# lpc1347_refboard.net
KiCad netlist of a schematic drawn in EAGLE
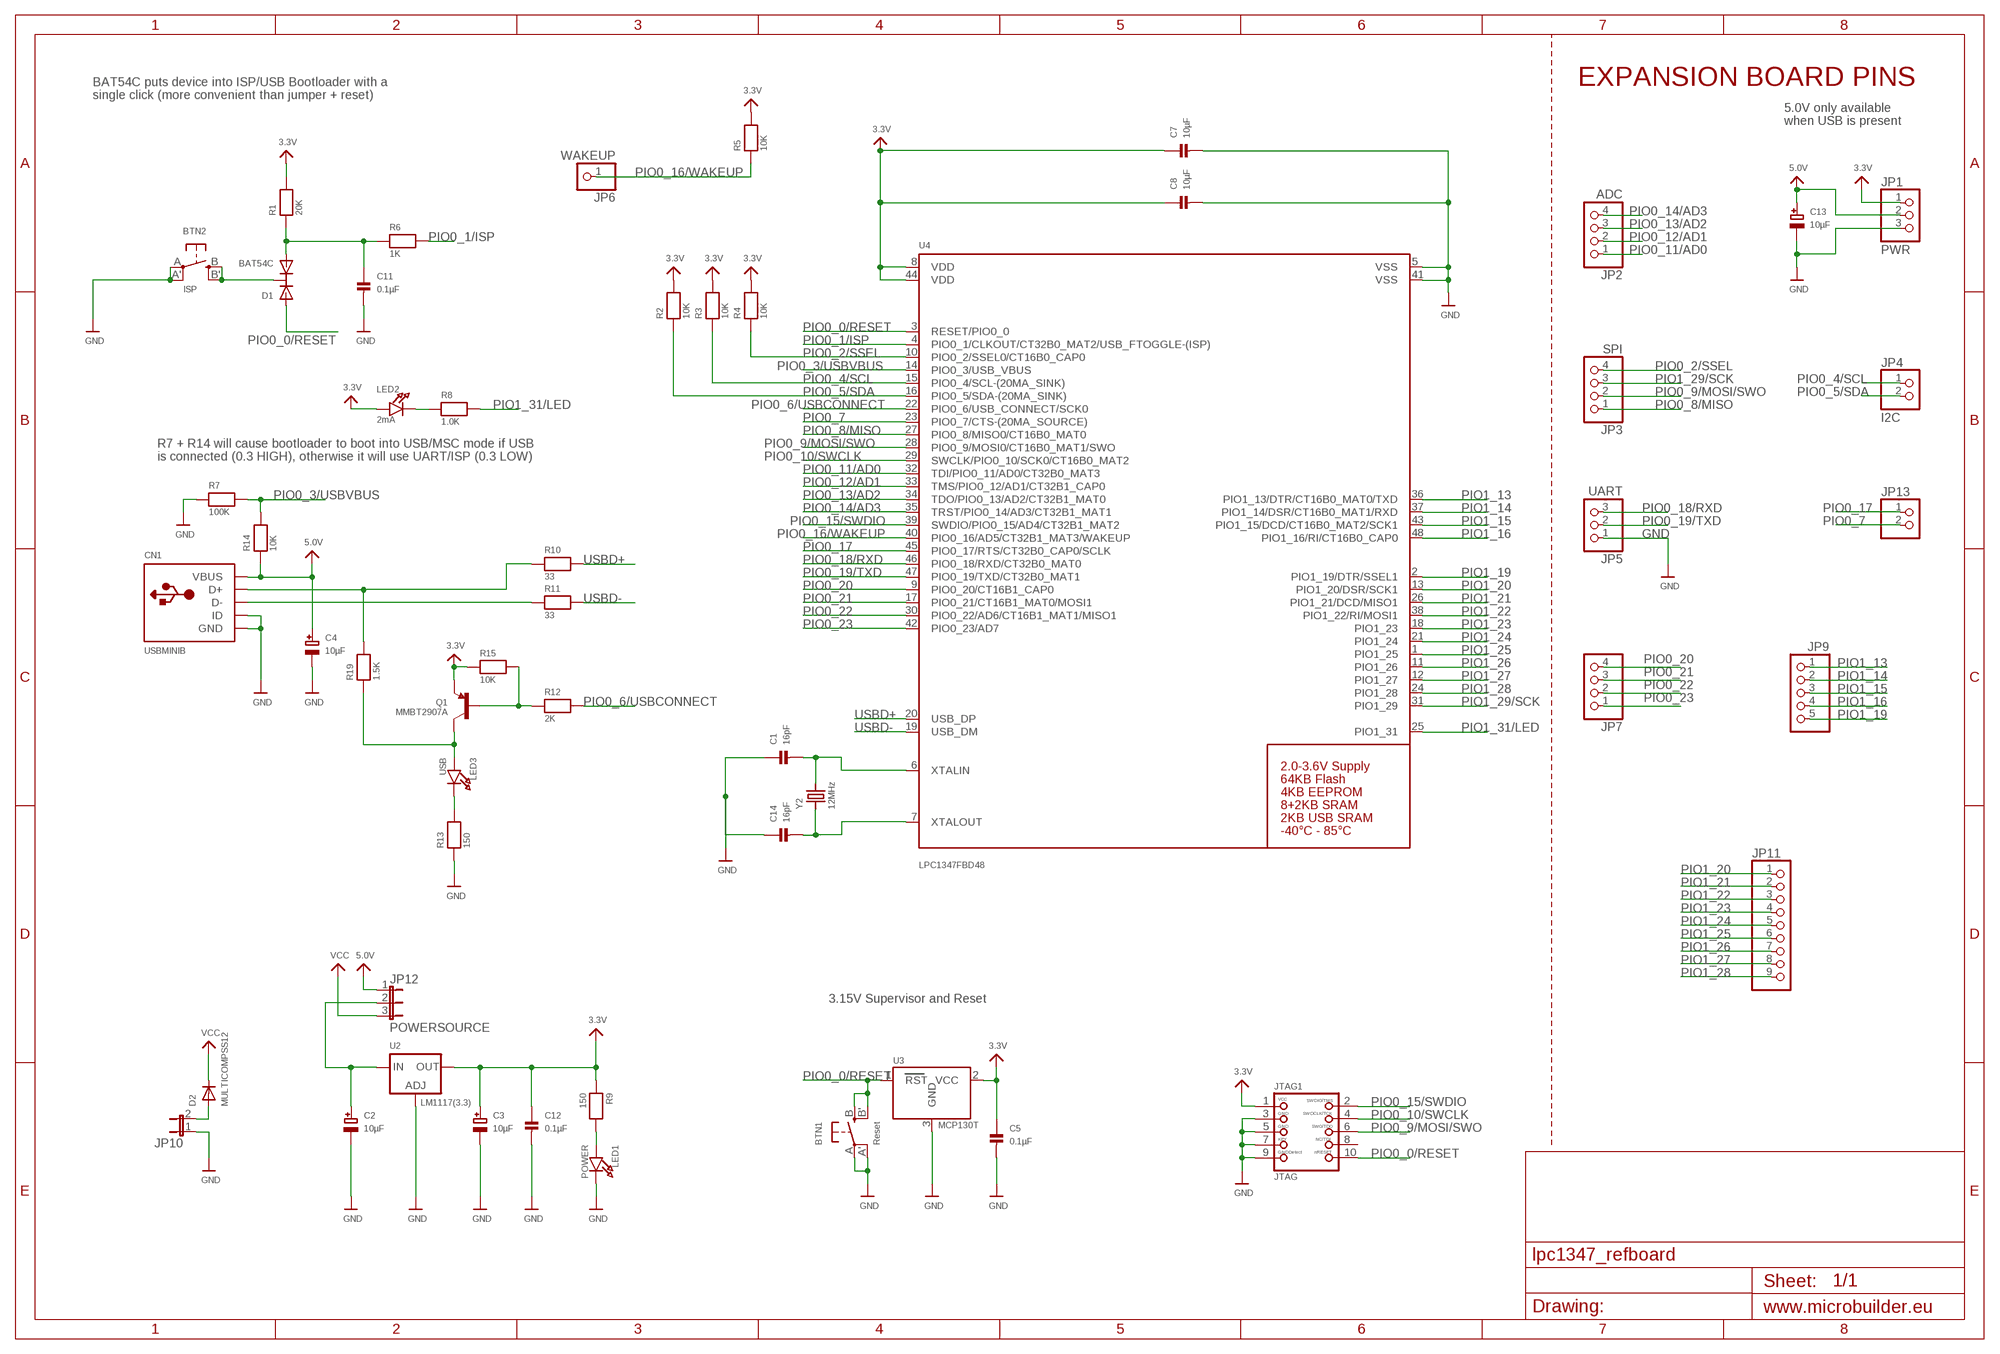
[diagram p0: schematic, sheet 1]

(export (version "E")
  (design (tool "Eeschema 10.0.6"))
  (components
    (comp (ref "BTN1")
      (value "Reset")
      (footprint "eagle-import:EVQ-Q2")
      (libsource (lib "eagle-import") (part "SWITCH_TACT_SMT"))
    )
    (comp (ref "BTN2")
      (value "ISP")
      (footprint "eagle-import:EVQ-Q2")
      (libsource (lib "eagle-import") (part "SWITCH_TACT_SMT"))
    )
    (comp (ref "C1")
      (value "16pF")
      (footprint "eagle-import:0603")
      (libsource (lib "eagle-import") (part "CAP_CERAMIC0603"))
    )
    (comp (ref "C2")
      (value "10µF")
      (footprint "eagle-import:EIA3216-18_A-R")
      (libsource (lib "eagle-import") (part "CAP_TANTALUMA/3216_REFLOW"))
    )
    (comp (ref "C3")
      (value "10µF")
      (footprint "eagle-import:EIA3216-18_A-R")
      (libsource (lib "eagle-import") (part "CAP_TANTALUMA/3216_REFLOW"))
    )
    (comp (ref "C4")
      (value "10µF")
      (footprint "eagle-import:EIA3216-18_A-R")
      (libsource (lib "eagle-import") (part "CAP_TANTALUMA/3216_REFLOW"))
    )
    (comp (ref "C5")
      (value "0.1µF")
      (footprint "eagle-import:0603")
      (libsource (lib "eagle-import") (part "CAP_CERAMIC0603"))
    )
    (comp (ref "C7")
      (value "10µF")
      (footprint "eagle-import:0805")
      (libsource (lib "eagle-import") (part "CAP_CERAMIC0805"))
    )
    (comp (ref "C8")
      (value "10µF")
      (footprint "eagle-import:0805")
      (libsource (lib "eagle-import") (part "CAP_CERAMIC0805"))
    )
    (comp (ref "C11")
      (value "0.1µF")
      (footprint "eagle-import:0603")
      (libsource (lib "eagle-import") (part "CAP_CERAMIC0603"))
    )
    (comp (ref "C12")
      (value "0.1µF")
      (footprint "eagle-import:0603")
      (libsource (lib "eagle-import") (part "CAP_CERAMIC0603"))
    )
    (comp (ref "C13")
      (value "10µF")
      (footprint "eagle-import:EIA3216-18_A-R")
      (libsource (lib "eagle-import") (part "CAP_TANTALUMA/3216_REFLOW"))
    )
    (comp (ref "C14")
      (value "16pF")
      (footprint "eagle-import:0603")
      (libsource (lib "eagle-import") (part "CAP_CERAMIC0603"))
    )
    (comp (ref "CN1")
      (value "USBMINIB")
      (footprint "eagle-import:USB-MINIB")
      (libsource (lib "eagle-import") (part "USBMINIB"))
    )
    (comp (ref "D1")
      (value "BAT54C")
      (footprint "eagle-import:SOT23-R")
      (libsource (lib "eagle-import") (part "BAT54C"))
    )
    (comp (ref "D2")
      (value "MULTICOMPSS12")
      (footprint "eagle-import:SMADIODE")
      (libsource (lib "eagle-import") (part "DIODESMA"))
    )
    (comp (ref "JP1")
      (value "PWR")
      (footprint "eagle-import:1X03_ROUND")
      (libsource (lib "eagle-import") (part "HEADER-1X3ROUND"))
    )
    (comp (ref "JP2")
      (value "ADC")
      (footprint "eagle-import:1X04_ROUND")
      (libsource (lib "eagle-import") (part "HEADER-1X4ROUND"))
    )
    (comp (ref "JP3")
      (value "SPI")
      (footprint "eagle-import:1X04_ROUND")
      (libsource (lib "eagle-import") (part "HEADER-1X4ROUND"))
    )
    (comp (ref "JP4")
      (value "I2C")
      (footprint "eagle-import:1X02_ROUND")
      (libsource (lib "eagle-import") (part "HEADER-1X2ROUND"))
    )
    (comp (ref "JP5")
      (value "UART")
      (footprint "eagle-import:1X03_ROUND")
      (libsource (lib "eagle-import") (part "microbuilder (1)_HEADER-1X3ROUND"))
    )
    (comp (ref "JP6")
      (value "WAKEUP")
      (footprint "eagle-import:1X01_ROUND")
      (libsource (lib "eagle-import") (part "HEADER-1X1ROUND"))
    )
    (comp (ref "JP7")
      (value "HEADER-1X4ROUND")
      (footprint "eagle-import:1X04_ROUND")
      (libsource (lib "eagle-import") (part "HEADER-1X4ROUND"))
    )
    (comp (ref "JP9")
      (value "HEADER-1X5ROUND")
      (footprint "eagle-import:1X05_ROUND")
      (libsource (lib "eagle-import") (part "HEADER-1X5ROUND"))
    )
    (comp (ref "JP10")
      (value "JUMPER2")
      (footprint "eagle-import:JUMPER2")
      (libsource (lib "eagle-import") (part "JUMPER2"))
    )
    (comp (ref "JP11")
      (value "HEADER-1X970MIL")
      (footprint "eagle-import:1X09_ROUND_70")
      (libsource (lib "eagle-import") (part "HEADER-1X970MIL"))
    )
    (comp (ref "JP12")
      (value "POWERSOURCE")
      (footprint "eagle-import:JUMPER3")
      (libsource (lib "eagle-import") (part "JUMPER3"))
    )
    (comp (ref "JP13")
      (value "HEADER-1X2ROUND")
      (footprint "eagle-import:1X02_ROUND")
      (libsource (lib "eagle-import") (part "HEADER-1X2ROUND"))
    )
    (comp (ref "JTAG1")
      (value "JTAG")
      (footprint "eagle-import:2X05_1.27MM_SMT")
      (libsource (lib "eagle-import") (part "JTAG-CORTEXM3"))
    )
    (comp (ref "LED1")
      (value "POWER")
      (footprint "eagle-import:CHIPLED_0805")
      (libsource (lib "eagle-import") (part "LED0805"))
    )
    (comp (ref "LED2")
      (value "2mA")
      (footprint "eagle-import:CHIPLED_0805")
      (libsource (lib "eagle-import") (part "LED0805"))
    )
    (comp (ref "LED3")
      (value "USB")
      (footprint "eagle-import:CHIPLED_0805")
      (libsource (lib "eagle-import") (part "LED0805"))
    )
    (comp (ref "Q1")
      (value "MMBT2907A")
      (footprint "eagle-import:SOT23-R")
      (libsource (lib "eagle-import") (part "TRANSISTOR_PNPSOT23-REFLOW"))
    )
    (comp (ref "R1")
      (value "20K")
      (footprint "eagle-import:0603")
      (libsource (lib "eagle-import") (part "RESISTOR0603"))
    )
    (comp (ref "R2")
      (value "10K")
      (footprint "eagle-import:0603")
      (libsource (lib "eagle-import") (part "RESISTOR0603"))
    )
    (comp (ref "R3")
      (value "10K")
      (footprint "eagle-import:0603")
      (libsource (lib "eagle-import") (part "RESISTOR0603"))
    )
    (comp (ref "R4")
      (value "10K")
      (footprint "eagle-import:0603")
      (libsource (lib "eagle-import") (part "RESISTOR0603"))
    )
    (comp (ref "R5")
      (value "10K")
      (footprint "eagle-import:0603")
      (libsource (lib "eagle-import") (part "RESISTOR0603"))
    )
    (comp (ref "R6")
      (value "1K")
      (footprint "eagle-import:0603")
      (libsource (lib "eagle-import") (part "RESISTOR0603"))
    )
    (comp (ref "R7")
      (value "100K")
      (footprint "eagle-import:0603")
      (libsource (lib "eagle-import") (part "RESISTOR0603"))
    )
    (comp (ref "R8")
      (value "1.0K")
      (footprint "eagle-import:0603")
      (libsource (lib "eagle-import") (part "RESISTOR0603"))
    )
    (comp (ref "R9")
      (value "150")
      (footprint "eagle-import:0603")
      (libsource (lib "eagle-import") (part "RESISTOR0603"))
    )
    (comp (ref "R10")
      (value "33")
      (footprint "eagle-import:0603")
      (libsource (lib "eagle-import") (part "RESISTOR0603"))
    )
    (comp (ref "R11")
      (value "33")
      (footprint "eagle-import:0603")
      (libsource (lib "eagle-import") (part "RESISTOR0603"))
    )
    (comp (ref "R12")
      (value "2K")
      (footprint "eagle-import:0603")
      (libsource (lib "eagle-import") (part "RESISTOR0603"))
    )
    (comp (ref "R13")
      (value "150")
      (footprint "eagle-import:0603")
      (libsource (lib "eagle-import") (part "RESISTOR0603"))
    )
    (comp (ref "R14")
      (value "10K")
      (footprint "eagle-import:0603")
      (libsource (lib "eagle-import") (part "RESISTOR0603"))
    )
    (comp (ref "R15")
      (value "10K")
      (footprint "eagle-import:0603")
      (libsource (lib "eagle-import") (part "RESISTOR0603"))
    )
    (comp (ref "R19")
      (value "1.5K")
      (footprint "eagle-import:0603")
      (libsource (lib "eagle-import") (part "RESISTOR0603"))
    )
    (comp (ref "U2")
      (value "LM1117(3.3)")
      (footprint "eagle-import:SOT223-R")
      (libsource (lib "eagle-import") (part "LM1117SOT223-REFLOW"))
    )
    (comp (ref "U3")
      (value "MCP130T")
      (footprint "eagle-import:SOT23-R")
      (libsource (lib "eagle-import") (part "MCP130TREFLOW"))
    )
    (comp (ref "U4")
      (value "LPC1347FBD48")
      (footprint "eagle-import:LQFP48")
      (libsource (lib "eagle-import") (part "LPC1347_QFP48"))
    )
    (comp (ref "Y2")
      (value "12MHz")
      (footprint "eagle-import:CRYSTAL_3.2X2.5")
      (libsource (lib "eagle-import") (part "CRYSTALTHIN"))
    )
  )
  (nets
    (net (code "1") (name "/PIO0_0{slash}RESET") (class "Default")
      (node (ref "BTN1") (pin "B") (pinfunction "S_B") (pintype "passive"))
      (node (ref "BTN1") (pin "B'") (pinfunction "S1_B'") (pintype "passive"))
      (node (ref "D1") (pin "1") (pinfunction "A1_1") (pintype "passive"))
      (node (ref "JTAG1") (pin "10") (pinfunction "10_10") (pintype "passive"))
      (node (ref "U3") (pin "1") (pinfunction "RST_1") (pintype "bidirectional"))
      (node (ref "U4") (pin "3") (pinfunction "RESET/PIO0_0_3") (pintype "bidirectional"))
    )
    (net (code "2") (name "/PIO0_1{slash}ISP") (class "Default")
      (node (ref "R6") (pin "2") (pinfunction "2_2") (pintype "passive"))
      (node (ref "U4") (pin "4") (pinfunction "PIO0_1/CLKOUT/CT32B0_MAT2/USB_FTOGGLE-(ISP)_4") (pintype "bidirectional"))
    )
    (net (code "3") (name "/PIO0_2{slash}SSEL") (class "Default")
      (node (ref "JP3") (pin "4") (pinfunction "4_4") (pintype "passive"))
      (node (ref "R4") (pin "1") (pinfunction "1_1") (pintype "passive"))
      (node (ref "U4") (pin "10") (pinfunction "PIO0_2/SSEL0/CT16B0_CAP0_10") (pintype "bidirectional"))
    )
    (net (code "4") (name "/PIO0_3{slash}USBVBUS") (class "Default")
      (node (ref "R14") (pin "2") (pinfunction "2_2") (pintype "passive"))
      (node (ref "R7") (pin "2") (pinfunction "2_2") (pintype "passive"))
      (node (ref "U4") (pin "14") (pinfunction "PIO0_3/USB_VBUS_14") (pintype "bidirectional"))
    )
    (net (code "5") (name "/PIO0_4{slash}SCL") (class "Default")
      (node (ref "JP4") (pin "1") (pinfunction "1_1") (pintype "passive"))
      (node (ref "R3") (pin "1") (pinfunction "1_1") (pintype "passive"))
      (node (ref "U4") (pin "15") (pinfunction "PIO0_4/SCL-(20MA_SINK)_15") (pintype "bidirectional"))
    )
    (net (code "6") (name "/PIO0_5{slash}SDA") (class "Default")
      (node (ref "JP4") (pin "2") (pinfunction "2_2") (pintype "passive"))
      (node (ref "R2") (pin "1") (pinfunction "1_1") (pintype "passive"))
      (node (ref "U4") (pin "16") (pinfunction "PIO0_5/SDA-(20MA_SINK)_16") (pintype "bidirectional"))
    )
    (net (code "7") (name "/PIO0_6{slash}USBCONNECT") (class "Default")
      (node (ref "R12") (pin "2") (pinfunction "2_2") (pintype "passive"))
      (node (ref "U4") (pin "22") (pinfunction "PIO0_6/USB_CONNECT/SCK0_22") (pintype "bidirectional"))
    )
    (net (code "8") (name "/PIO0_7") (class "Default")
      (node (ref "JP13") (pin "2") (pinfunction "2_2") (pintype "passive"))
      (node (ref "U4") (pin "23") (pinfunction "PIO0_7/CTS-(20MA_SOURCE)_23") (pintype "bidirectional"))
    )
    (net (code "9") (name "/PIO0_8{slash}MISO") (class "Default")
      (node (ref "JP3") (pin "1") (pinfunction "1_1") (pintype "passive"))
      (node (ref "U4") (pin "27") (pinfunction "PIO0_8/MISO0/CT16B0_MAT0_27") (pintype "bidirectional"))
    )
    (net (code "10") (name "/PIO0_9{slash}MOSI{slash}SWO") (class "Default")
      (node (ref "JP3") (pin "2") (pinfunction "2_2") (pintype "passive"))
      (node (ref "JTAG1") (pin "6") (pinfunction "6_6") (pintype "passive"))
      (node (ref "U4") (pin "28") (pinfunction "PIO0_9/MOSI0/CT16B0_MAT1/SWO_28") (pintype "bidirectional"))
    )
    (net (code "11") (name "/PIO0_10{slash}SWCLK") (class "Default")
      (node (ref "JTAG1") (pin "4") (pinfunction "4_4") (pintype "passive"))
      (node (ref "U4") (pin "29") (pinfunction "SWCLK/PIO0_10/SCK0/CT16B0_MAT2_29") (pintype "bidirectional"))
    )
    (net (code "12") (name "/PIO0_11{slash}AD0") (class "Default")
      (node (ref "JP2") (pin "1") (pinfunction "1_1") (pintype "passive"))
      (node (ref "U4") (pin "32") (pinfunction "TDI/PIO0_11/AD0/CT32B0_MAT3_32") (pintype "bidirectional"))
    )
    (net (code "13") (name "/PIO0_12{slash}AD1") (class "Default")
      (node (ref "JP2") (pin "2") (pinfunction "2_2") (pintype "passive"))
      (node (ref "U4") (pin "33") (pinfunction "TMS/PIO0_12/AD1/CT32B1_CAP0_33") (pintype "bidirectional"))
    )
    (net (code "14") (name "/PIO0_13{slash}AD2") (class "Default")
      (node (ref "JP2") (pin "3") (pinfunction "3_3") (pintype "passive"))
      (node (ref "U4") (pin "34") (pinfunction "TDO/PIO0_13/AD2/CT32B1_MAT0_34") (pintype "bidirectional"))
    )
    (net (code "15") (name "/PIO0_14{slash}AD3") (class "Default")
      (node (ref "JP2") (pin "4") (pinfunction "4_4") (pintype "passive"))
      (node (ref "U4") (pin "35") (pinfunction "TRST/PIO0_14/AD3/CT32B1_MAT1_35") (pintype "bidirectional"))
    )
    (net (code "16") (name "/PIO0_15{slash}SWDIO") (class "Default")
      (node (ref "JTAG1") (pin "2") (pinfunction "2_2") (pintype "passive"))
      (node (ref "U4") (pin "39") (pinfunction "SWDIO/PIO0_15/AD4/CT32B1_MAT2_39") (pintype "bidirectional"))
    )
    (net (code "17") (name "/PIO0_16{slash}WAKEUP") (class "Default")
      (node (ref "JP6") (pin "1") (pinfunction "1_1") (pintype "passive"))
      (node (ref "R5") (pin "1") (pinfunction "1_1") (pintype "passive"))
      (node (ref "U4") (pin "40") (pinfunction "PIO0_16/AD5/CT32B1_MAT3/WAKEUP_40") (pintype "bidirectional"))
    )
    (net (code "18") (name "/PIO0_17") (class "Default")
      (node (ref "JP13") (pin "1") (pinfunction "1_1") (pintype "passive"))
      (node (ref "U4") (pin "45") (pinfunction "PIO0_17/RTS/CT32B0_CAP0/SCLK_45") (pintype "bidirectional"))
    )
    (net (code "19") (name "/PIO0_18{slash}RXD") (class "Default")
      (node (ref "JP5") (pin "3") (pinfunction "3_3") (pintype "passive"))
      (node (ref "U4") (pin "46") (pinfunction "PIO0_18/RXD/CT32B0_MAT0_46") (pintype "bidirectional"))
    )
    (net (code "20") (name "/PIO0_19{slash}TXD") (class "Default")
      (node (ref "JP5") (pin "2") (pinfunction "2_2") (pintype "passive"))
      (node (ref "U4") (pin "47") (pinfunction "PIO0_19/TXD/CT32B0_MAT1_47") (pintype "bidirectional"))
    )
    (net (code "21") (name "/PIO0_20") (class "Default")
      (node (ref "JP7") (pin "4") (pinfunction "4_4") (pintype "passive"))
      (node (ref "U4") (pin "9") (pinfunction "PIO0_20/CT16B1_CAP0_9") (pintype "bidirectional"))
    )
    (net (code "22") (name "/PIO0_21") (class "Default")
      (node (ref "JP7") (pin "3") (pinfunction "3_3") (pintype "passive"))
      (node (ref "U4") (pin "17") (pinfunction "PIO0_21/CT16B1_MAT0/MOSI1_17") (pintype "bidirectional"))
    )
    (net (code "23") (name "/PIO0_22") (class "Default")
      (node (ref "JP7") (pin "2") (pinfunction "2_2") (pintype "passive"))
      (node (ref "U4") (pin "30") (pinfunction "PIO0_22/AD6/CT16B1_MAT1/MISO1_30") (pintype "bidirectional"))
    )
    (net (code "24") (name "/PIO0_23") (class "Default")
      (node (ref "JP7") (pin "1") (pinfunction "1_1") (pintype "passive"))
      (node (ref "U4") (pin "42") (pinfunction "PIO0_23/AD7_42") (pintype "bidirectional"))
    )
    (net (code "25") (name "/PIO1_13") (class "Default")
      (node (ref "JP9") (pin "1") (pinfunction "1_1") (pintype "passive"))
      (node (ref "U4") (pin "36") (pinfunction "PIO1_13/DTR/CT16B0_MAT0/TXD_36") (pintype "bidirectional"))
    )
    (net (code "26") (name "/PIO1_14") (class "Default")
      (node (ref "JP9") (pin "2") (pinfunction "2_2") (pintype "passive"))
      (node (ref "U4") (pin "37") (pinfunction "PIO1_14/DSR/CT16B0_MAT1/RXD_37") (pintype "bidirectional"))
    )
    (net (code "27") (name "/PIO1_15") (class "Default")
      (node (ref "JP9") (pin "3") (pinfunction "3_3") (pintype "passive"))
      (node (ref "U4") (pin "43") (pinfunction "PIO1_15/DCD/CT16B0_MAT2/SCK1_43") (pintype "bidirectional"))
    )
    (net (code "28") (name "/PIO1_16") (class "Default")
      (node (ref "JP9") (pin "4") (pinfunction "4_4") (pintype "passive"))
      (node (ref "U4") (pin "48") (pinfunction "PIO1_16/RI/CT16B0_CAP0_48") (pintype "bidirectional"))
    )
    (net (code "29") (name "/PIO1_19") (class "Default")
      (node (ref "JP9") (pin "5") (pinfunction "5_5") (pintype "passive"))
      (node (ref "U4") (pin "2") (pinfunction "PIO1_19/DTR/SSEL1_2") (pintype "bidirectional"))
    )
    (net (code "30") (name "/PIO1_20") (class "Default")
      (node (ref "JP11") (pin "1") (pinfunction "1_1") (pintype "passive"))
      (node (ref "U4") (pin "13") (pinfunction "PIO1_20/DSR/SCK1_13") (pintype "bidirectional"))
    )
    (net (code "31") (name "/PIO1_21") (class "Default")
      (node (ref "JP11") (pin "2") (pinfunction "2_2") (pintype "passive"))
      (node (ref "U4") (pin "26") (pinfunction "PIO1_21/DCD/MISO1_26") (pintype "bidirectional"))
    )
    (net (code "32") (name "/PIO1_22") (class "Default")
      (node (ref "JP11") (pin "3") (pinfunction "3_3") (pintype "passive"))
      (node (ref "U4") (pin "38") (pinfunction "PIO1_22/RI/MOSI1_38") (pintype "bidirectional"))
    )
    (net (code "33") (name "/PIO1_23") (class "Default")
      (node (ref "JP11") (pin "4") (pinfunction "4_4") (pintype "passive"))
      (node (ref "U4") (pin "18") (pinfunction "PIO1_23_18") (pintype "bidirectional"))
    )
    (net (code "34") (name "/PIO1_24") (class "Default")
      (node (ref "JP11") (pin "5") (pinfunction "5_5") (pintype "passive"))
      (node (ref "U4") (pin "21") (pinfunction "PIO1_24_21") (pintype "bidirectional"))
    )
    (net (code "35") (name "/PIO1_25") (class "Default")
      (node (ref "JP11") (pin "6") (pinfunction "6_6") (pintype "passive"))
      (node (ref "U4") (pin "1") (pinfunction "PIO1_25_1") (pintype "bidirectional"))
    )
    (net (code "36") (name "/PIO1_26") (class "Default")
      (node (ref "JP11") (pin "7") (pinfunction "7_7") (pintype "passive"))
      (node (ref "U4") (pin "11") (pinfunction "PIO1_26_11") (pintype "bidirectional"))
    )
    (net (code "37") (name "/PIO1_27") (class "Default")
      (node (ref "JP11") (pin "8") (pinfunction "8_8") (pintype "passive"))
      (node (ref "U4") (pin "12") (pinfunction "PIO1_27_12") (pintype "bidirectional"))
    )
    (net (code "38") (name "/PIO1_28") (class "Default")
      (node (ref "JP11") (pin "9") (pinfunction "9_9") (pintype "passive"))
      (node (ref "U4") (pin "24") (pinfunction "PIO1_28_24") (pintype "bidirectional"))
    )
    (net (code "39") (name "/PIO1_29{slash}SCK") (class "Default")
      (node (ref "JP3") (pin "3") (pinfunction "3_3") (pintype "passive"))
      (node (ref "U4") (pin "31") (pinfunction "PIO1_29_31") (pintype "bidirectional"))
    )
    (net (code "40") (name "/PIO1_31{slash}LED") (class "Default")
      (node (ref "R8") (pin "2") (pinfunction "2_2") (pintype "passive"))
      (node (ref "U4") (pin "25") (pinfunction "PIO1_31_25") (pintype "bidirectional"))
    )
    (net (code "41") (name "/USBD+") (class "Default")
      (node (ref "R10") (pin "2") (pinfunction "2_2") (pintype "passive"))
      (node (ref "U4") (pin "20") (pinfunction "USB_DP_20") (pintype "bidirectional"))
    )
    (net (code "42") (name "/USBD-") (class "Default")
      (node (ref "R11") (pin "2") (pinfunction "2_2") (pintype "passive"))
      (node (ref "U4") (pin "19") (pinfunction "USB_DM_19") (pintype "bidirectional"))
    )
    (net (code "43") (name "3.3V") (class "Default")
      (node (ref "C12") (pin "1") (pinfunction "P$1_1") (pintype "passive"))
      (node (ref "C3") (pin "+") (pinfunction "+_+") (pintype "passive"))
      (node (ref "C5") (pin "1") (pinfunction "P$1_1") (pintype "passive"))
      (node (ref "C7") (pin "1") (pinfunction "P$1_1") (pintype "passive"))
      (node (ref "C8") (pin "1") (pinfunction "P$1_1") (pintype "passive"))
      (node (ref "JP1") (pin "1") (pinfunction "1_1") (pintype "passive"))
      (node (ref "JTAG1") (pin "1") (pinfunction "1_1") (pintype "passive"))
      (node (ref "LED2") (pin "A") (pinfunction "A_A") (pintype "passive"))
      (node (ref "Q1") (pin "2") (pinfunction "E_2") (pintype "passive"))
      (node (ref "R1") (pin "2") (pinfunction "2_2") (pintype "passive"))
      (node (ref "R15") (pin "1") (pinfunction "1_1") (pintype "passive"))
      (node (ref "R2") (pin "2") (pinfunction "2_2") (pintype "passive"))
      (node (ref "R3") (pin "2") (pinfunction "2_2") (pintype "passive"))
      (node (ref "R4") (pin "2") (pinfunction "2_2") (pintype "passive"))
      (node (ref "R5") (pin "2") (pinfunction "2_2") (pintype "passive"))
      (node (ref "R9") (pin "1") (pinfunction "1_1") (pintype "passive"))
      (node (ref "U2") (pin "2") (pinfunction "OUT_2") (pintype "passive"))
      (node (ref "U3") (pin "2") (pinfunction "VCC_2") (pintype "power_in"))
      (node (ref "U4") (pin "44") (pinfunction "VDD_44") (pintype "power_in"))
      (node (ref "U4") (pin "8") (pinfunction "VDD_8") (pintype "power_in"))
    )
    (net (code "44") (name "5.0V") (class "Default")
      (node (ref "C13") (pin "+") (pinfunction "+_+") (pintype "passive"))
      (node (ref "C4") (pin "+") (pinfunction "+_+") (pintype "passive"))
      (node (ref "CN1") (pin "VBUS") (pinfunction "VBUS_VBUS") (pintype "power_in"))
      (node (ref "JP1") (pin "2") (pinfunction "2_2") (pintype "passive"))
      (node (ref "JP12") (pin "1") (pinfunction "1_1") (pintype "passive"))
      (node (ref "R14") (pin "1") (pinfunction "1_1") (pintype "passive"))
    )
    (net (code "45") (name "GND") (class "Default")
      (node (ref "BTN1") (pin "A") (pinfunction "P_A") (pintype "passive"))
      (node (ref "BTN1") (pin "A'") (pinfunction "P1_A'") (pintype "passive"))
      (node (ref "BTN2") (pin "A") (pinfunction "P_A") (pintype "passive"))
      (node (ref "BTN2") (pin "A'") (pinfunction "P1_A'") (pintype "passive"))
      (node (ref "C1") (pin "1") (pinfunction "P$1_1") (pintype "passive"))
      (node (ref "C11") (pin "2") (pinfunction "P$2_2") (pintype "passive"))
      (node (ref "C12") (pin "2") (pinfunction "P$2_2") (pintype "passive"))
      (node (ref "C13") (pin "-") (pinfunction "-_-") (pintype "passive"))
      (node (ref "C14") (pin "1") (pinfunction "P$1_1") (pintype "passive"))
      (node (ref "C2") (pin "-") (pinfunction "-_-") (pintype "passive"))
      (node (ref "C3") (pin "-") (pinfunction "-_-") (pintype "passive"))
      (node (ref "C4") (pin "-") (pinfunction "-_-") (pintype "passive"))
      (node (ref "C5") (pin "2") (pinfunction "P$2_2") (pintype "passive"))
      (node (ref "C7") (pin "2") (pinfunction "P$2_2") (pintype "passive"))
      (node (ref "C8") (pin "2") (pinfunction "P$2_2") (pintype "passive"))
      (node (ref "CN1") (pin "GND") (pinfunction "GND_GND") (pintype "power_in"))
      (node (ref "CN1") (pin "ID") (pinfunction "ID_ID") (pintype "bidirectional"))
      (node (ref "JP1") (pin "3") (pinfunction "3_3") (pintype "passive"))
      (node (ref "JP10") (pin "1") (pinfunction "1_1") (pintype "passive"))
      (node (ref "JP5") (pin "1") (pinfunction "1_1") (pintype "passive"))
      (node (ref "JTAG1") (pin "3") (pinfunction "3_3") (pintype "passive"))
      (node (ref "JTAG1") (pin "5") (pinfunction "5_5") (pintype "passive"))
      (node (ref "JTAG1") (pin "7") (pinfunction "7_7") (pintype "passive"))
      (node (ref "JTAG1") (pin "9") (pinfunction "9_9") (pintype "passive"))
      (node (ref "LED1") (pin "C") (pinfunction "C_C") (pintype "passive"))
      (node (ref "R13") (pin "1") (pinfunction "1_1") (pintype "passive"))
      (node (ref "R7") (pin "1") (pinfunction "1_1") (pintype "passive"))
      (node (ref "U2") (pin "1") (pinfunction "ADJ_1") (pintype "input"))
      (node (ref "U3") (pin "3") (pinfunction "GND_3") (pintype "power_in"))
      (node (ref "U4") (pin "41") (pinfunction "VSS_41") (pintype "power_in"))
      (node (ref "U4") (pin "5") (pinfunction "VSS_5") (pintype "power_in"))
    )
    (net (code "46") (name "Net-(BTN2-S)") (class "Default")
      (node (ref "BTN2") (pin "B") (pinfunction "S_B") (pintype "passive"))
      (node (ref "BTN2") (pin "B'") (pinfunction "S1_B'") (pintype "passive"))
      (node (ref "D1") (pin "3") (pinfunction "C_3") (pintype "passive"))
    )
    (net (code "47") (name "Net-(C1-P$2)") (class "Default")
      (node (ref "C1") (pin "2") (pinfunction "P$2_2") (pintype "passive"))
      (node (ref "U4") (pin "6") (pinfunction "XTALIN_6") (pintype "bidirectional"))
      (node (ref "Y2") (pin "2") (pinfunction "2_2") (pintype "passive"))
    )
    (net (code "48") (name "Net-(C11-P$1)") (class "Default")
      (node (ref "C11") (pin "1") (pinfunction "P$1_1") (pintype "passive"))
      (node (ref "D1") (pin "2") (pinfunction "A2_2") (pintype "passive"))
      (node (ref "R1") (pin "1") (pinfunction "1_1") (pintype "passive"))
      (node (ref "R6") (pin "1") (pinfunction "1_1") (pintype "passive"))
    )
    (net (code "49") (name "Net-(C14-P$2)") (class "Default")
      (node (ref "C14") (pin "2") (pinfunction "P$2_2") (pintype "passive"))
      (node (ref "U4") (pin "7") (pinfunction "XTALOUT_7") (pintype "bidirectional"))
      (node (ref "Y2") (pin "1") (pinfunction "1_1") (pintype "passive"))
    )
    (net (code "50") (name "Net-(CN1-PadD+)") (class "Default")
      (node (ref "CN1") (pin "D+") (pinfunction "D+_D+") (pintype "bidirectional"))
      (node (ref "R10") (pin "1") (pinfunction "1_1") (pintype "passive"))
      (node (ref "R19") (pin "2") (pinfunction "2_2") (pintype "passive"))
    )
    (net (code "51") (name "Net-(CN1-PadD-)") (class "Default")
      (node (ref "CN1") (pin "D-") (pinfunction "D-_D-") (pintype "bidirectional"))
      (node (ref "R11") (pin "1") (pinfunction "1_1") (pintype "passive"))
    )
    (net (code "52") (name "Net-(D2-PadA)") (class "Default")
      (node (ref "D2") (pin "A") (pinfunction "A_A") (pintype "passive"))
      (node (ref "JP10") (pin "2") (pinfunction "2_2") (pintype "passive"))
    )
    (net (code "53") (name "Net-(LED1-PadA)") (class "Default")
      (node (ref "LED1") (pin "A") (pinfunction "A_A") (pintype "passive"))
      (node (ref "R9") (pin "2") (pinfunction "2_2") (pintype "passive"))
    )
    (net (code "54") (name "Net-(LED2-PadC)") (class "Default")
      (node (ref "LED2") (pin "C") (pinfunction "C_C") (pintype "passive"))
      (node (ref "R8") (pin "1") (pinfunction "1_1") (pintype "passive"))
    )
    (net (code "55") (name "Net-(LED3-PadC)") (class "Default")
      (node (ref "LED3") (pin "C") (pinfunction "C_C") (pintype "passive"))
      (node (ref "R13") (pin "2") (pinfunction "2_2") (pintype "passive"))
    )
    (net (code "56") (name "Net-(Q1-B)") (class "Default")
      (node (ref "Q1") (pin "1") (pinfunction "B_1") (pintype "passive"))
      (node (ref "R12") (pin "1") (pinfunction "1_1") (pintype "passive"))
      (node (ref "R15") (pin "2") (pinfunction "2_2") (pintype "passive"))
    )
    (net (code "57") (name "Net-(Q1-C)") (class "Default")
      (node (ref "LED3") (pin "A") (pinfunction "A_A") (pintype "passive"))
      (node (ref "Q1") (pin "3") (pinfunction "C_3") (pintype "passive"))
      (node (ref "R19") (pin "1") (pinfunction "1_1") (pintype "passive"))
    )
    (net (code "58") (name "Net-(U2-IN)") (class "Default")
      (node (ref "C2") (pin "+") (pinfunction "+_+") (pintype "passive"))
      (node (ref "JP12") (pin "2") (pinfunction "2_2") (pintype "passive"))
      (node (ref "U2") (pin "3") (pinfunction "IN_3") (pintype "input"))
    )
    (net (code "59") (name "VCC") (class "Default")
      (node (ref "D2") (pin "C") (pinfunction "C_C") (pintype "passive"))
      (node (ref "JP12") (pin "3") (pinfunction "3_3") (pintype "passive"))
    )
    (net (code "60") (name "unconnected-(JTAG1-Pad8)") (class "Default")
      (node (ref "JTAG1") (pin "8") (pinfunction "8_8") (pintype "passive"))
    )
  )
)
